# imx6_power.net
KiCad netlist of a schematic drawn in Altium Designer
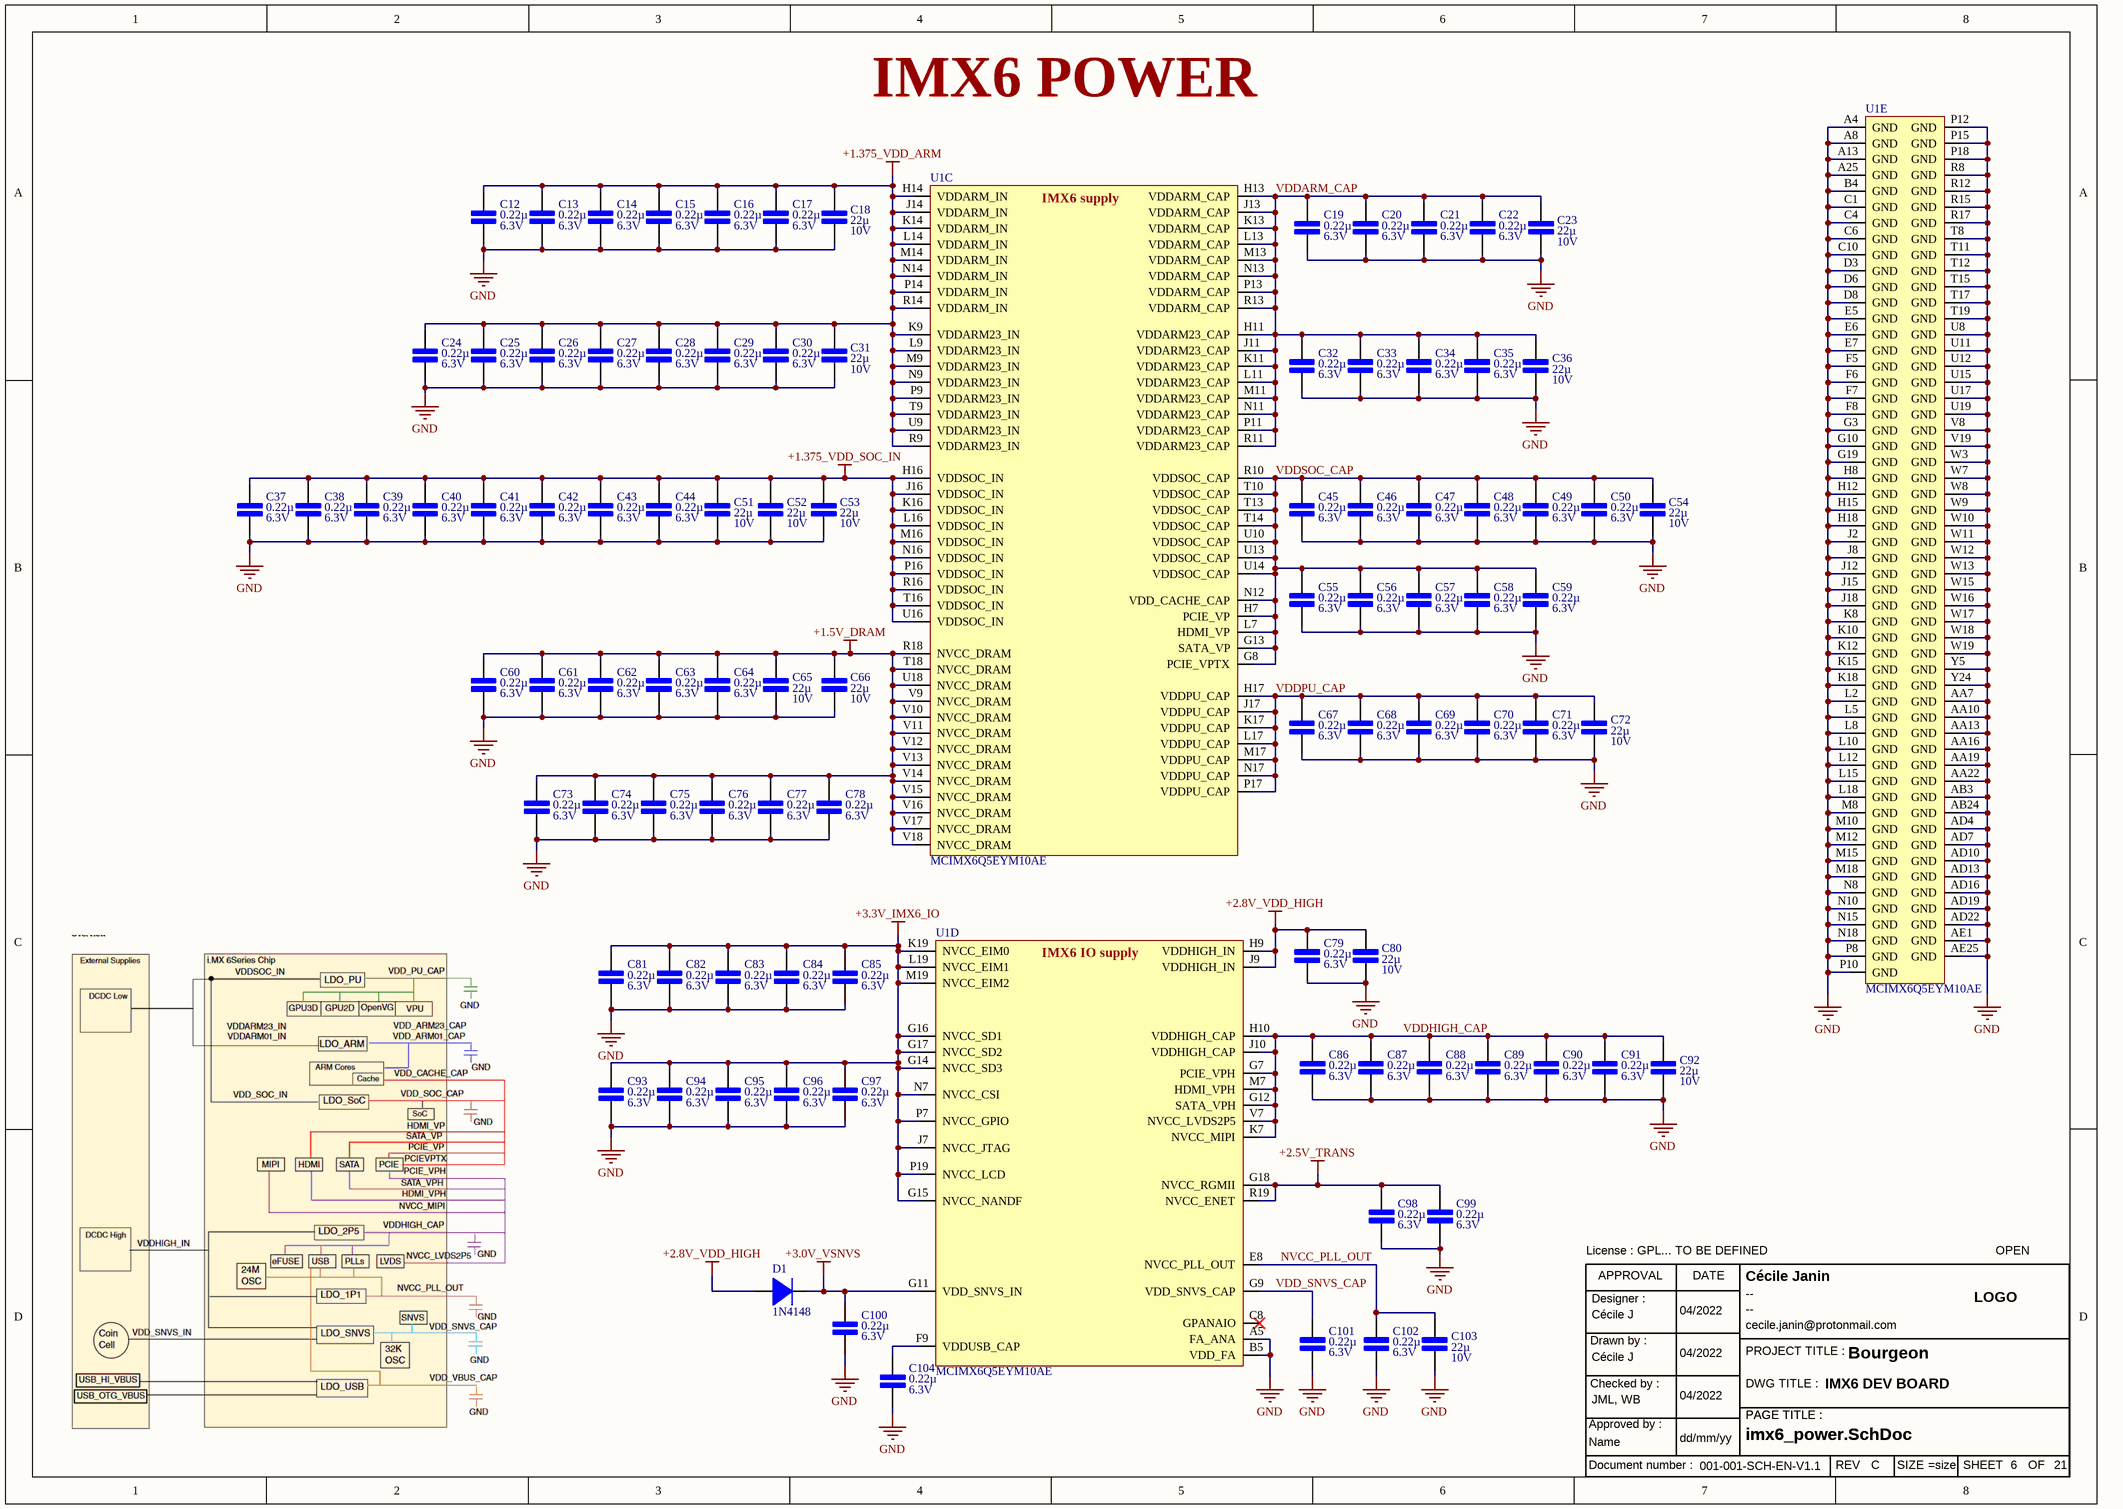
[diagram p0: imx6_power.SchDoc]

(export (version "E")
  (design (tool "Eeschema 10.0.6"))
  (components
    (comp (ref "C12")
      (value "0.22µ")
      (footprint "CAP CER 0201/0603")
      (description "cap solid electrolyte 0.22µ 6.3V 10%")
      (fields (field (name "TENSION DU DIÉLECTRIQUE") "6.3V"))
      (libsource (lib "First Board IMX6") (part "cap 0.22µ 6.3V"))
    )
    (comp (ref "C13")
      (value "0.22µ")
      (footprint "CAP CER 0201/0603")
      (description "cap solid electrolyte 0.22µ 6.3V 10%")
      (fields (field (name "TENSION DU DIÉLECTRIQUE") "6.3V"))
      (libsource (lib "First Board IMX6") (part "cap 0.22µ 6.3V"))
    )
    (comp (ref "C14")
      (value "0.22µ")
      (footprint "CAP CER 0201/0603")
      (description "cap solid electrolyte 0.22µ 6.3V 10%")
      (fields (field (name "TENSION DU DIÉLECTRIQUE") "6.3V"))
      (libsource (lib "First Board IMX6") (part "cap 0.22µ 6.3V"))
    )
    (comp (ref "C15")
      (value "0.22µ")
      (footprint "CAP CER 0201/0603")
      (description "cap solid electrolyte 0.22µ 6.3V 10%")
      (fields (field (name "TENSION DU DIÉLECTRIQUE") "6.3V"))
      (libsource (lib "First Board IMX6") (part "cap 0.22µ 6.3V"))
    )
    (comp (ref "C16")
      (value "0.22µ")
      (footprint "CAP CER 0201/0603")
      (description "cap solid electrolyte 0.22µ 6.3V 10%")
      (fields (field (name "TENSION DU DIÉLECTRIQUE") "6.3V"))
      (libsource (lib "First Board IMX6") (part "cap 0.22µ 6.3V"))
    )
    (comp (ref "C17")
      (value "0.22µ")
      (footprint "CAP CER 0201/0603")
      (description "cap solid electrolyte 0.22µ 6.3V 10%")
      (fields (field (name "TENSION DU DIÉLECTRIQUE") "6.3V"))
      (libsource (lib "First Board IMX6") (part "cap 0.22µ 6.3V"))
    )
    (comp (ref "C18")
      (value "22µ")
      (footprint "Cap cer 0603/4608")
      (description "cap cer 22µ 10V 10% X5R 0603")
      (fields (field (name "TENSION DU DIÉLECTRIQUE") "10V"))
      (libsource (lib "First Board IMX6") (part "cap 22µ 10V"))
    )
    (comp (ref "C19")
      (value "0.22µ")
      (footprint "CAP CER 0201/0603")
      (description "cap solid electrolyte 0.22µ 6.3V 10%")
      (fields (field (name "TENSION DU DIÉLECTRIQUE") "6.3V"))
      (libsource (lib "First Board IMX6") (part "cap 0.22µ 6.3V"))
    )
    (comp (ref "C20")
      (value "0.22µ")
      (footprint "CAP CER 0201/0603")
      (description "cap solid electrolyte 0.22µ 6.3V 10%")
      (fields (field (name "TENSION DU DIÉLECTRIQUE") "6.3V"))
      (libsource (lib "First Board IMX6") (part "cap 0.22µ 6.3V"))
    )
    (comp (ref "C21")
      (value "0.22µ")
      (footprint "CAP CER 0201/0603")
      (description "cap solid electrolyte 0.22µ 6.3V 10%")
      (fields (field (name "TENSION DU DIÉLECTRIQUE") "6.3V"))
      (libsource (lib "First Board IMX6") (part "cap 0.22µ 6.3V"))
    )
    (comp (ref "C22")
      (value "0.22µ")
      (footprint "CAP CER 0201/0603")
      (description "cap solid electrolyte 0.22µ 6.3V 10%")
      (fields (field (name "TENSION DU DIÉLECTRIQUE") "6.3V"))
      (libsource (lib "First Board IMX6") (part "cap 0.22µ 6.3V"))
    )
    (comp (ref "C23")
      (value "22µ")
      (footprint "Cap cer 0603/4608")
      (description "cap cer 22µ 10V 10% X5R 0603")
      (fields (field (name "TENSION DU DIÉLECTRIQUE") "10V"))
      (libsource (lib "First Board IMX6") (part "cap 22µ 10V"))
    )
    (comp (ref "C24")
      (value "0.22µ")
      (footprint "CAP CER 0201/0603")
      (description "cap solid electrolyte 0.22µ 6.3V 10%")
      (fields (field (name "TENSION DU DIÉLECTRIQUE") "6.3V"))
      (libsource (lib "First Board IMX6") (part "cap 0.22µ 6.3V"))
    )
    (comp (ref "C25")
      (value "0.22µ")
      (footprint "CAP CER 0201/0603")
      (description "cap solid electrolyte 0.22µ 6.3V 10%")
      (fields (field (name "TENSION DU DIÉLECTRIQUE") "6.3V"))
      (libsource (lib "First Board IMX6") (part "cap 0.22µ 6.3V"))
    )
    (comp (ref "C26")
      (value "0.22µ")
      (footprint "CAP CER 0201/0603")
      (description "cap solid electrolyte 0.22µ 6.3V 10%")
      (fields (field (name "TENSION DU DIÉLECTRIQUE") "6.3V"))
      (libsource (lib "First Board IMX6") (part "cap 0.22µ 6.3V"))
    )
    (comp (ref "C27")
      (value "0.22µ")
      (footprint "CAP CER 0201/0603")
      (description "cap solid electrolyte 0.22µ 6.3V 10%")
      (fields (field (name "TENSION DU DIÉLECTRIQUE") "6.3V"))
      (libsource (lib "First Board IMX6") (part "cap 0.22µ 6.3V"))
    )
    (comp (ref "C28")
      (value "0.22µ")
      (footprint "CAP CER 0201/0603")
      (description "cap solid electrolyte 0.22µ 6.3V 10%")
      (fields (field (name "TENSION DU DIÉLECTRIQUE") "6.3V"))
      (libsource (lib "First Board IMX6") (part "cap 0.22µ 6.3V"))
    )
    (comp (ref "C29")
      (value "0.22µ")
      (footprint "CAP CER 0201/0603")
      (description "cap solid electrolyte 0.22µ 6.3V 10%")
      (fields (field (name "TENSION DU DIÉLECTRIQUE") "6.3V"))
      (libsource (lib "First Board IMX6") (part "cap 0.22µ 6.3V"))
    )
    (comp (ref "C30")
      (value "0.22µ")
      (footprint "CAP CER 0201/0603")
      (description "cap solid electrolyte 0.22µ 6.3V 10%")
      (fields (field (name "TENSION DU DIÉLECTRIQUE") "6.3V"))
      (libsource (lib "First Board IMX6") (part "cap 0.22µ 6.3V"))
    )
    (comp (ref "C31")
      (value "22µ")
      (footprint "Cap cer 0603/4608")
      (description "cap cer 22µ 10V 10% X5R 0603")
      (fields (field (name "TENSION DU DIÉLECTRIQUE") "10V"))
      (libsource (lib "First Board IMX6") (part "cap 22µ 10V"))
    )
    (comp (ref "C32")
      (value "0.22µ")
      (footprint "CAP CER 0201/0603")
      (description "cap solid electrolyte 0.22µ 6.3V 10%")
      (fields (field (name "TENSION DU DIÉLECTRIQUE") "6.3V"))
      (libsource (lib "First Board IMX6") (part "cap 0.22µ 6.3V"))
    )
    (comp (ref "C33")
      (value "0.22µ")
      (footprint "CAP CER 0201/0603")
      (description "cap solid electrolyte 0.22µ 6.3V 10%")
      (fields (field (name "TENSION DU DIÉLECTRIQUE") "6.3V"))
      (libsource (lib "First Board IMX6") (part "cap 0.22µ 6.3V"))
    )
    (comp (ref "C34")
      (value "0.22µ")
      (footprint "CAP CER 0201/0603")
      (description "cap solid electrolyte 0.22µ 6.3V 10%")
      (fields (field (name "TENSION DU DIÉLECTRIQUE") "6.3V"))
      (libsource (lib "First Board IMX6") (part "cap 0.22µ 6.3V"))
    )
    (comp (ref "C35")
      (value "0.22µ")
      (footprint "CAP CER 0201/0603")
      (description "cap solid electrolyte 0.22µ 6.3V 10%")
      (fields (field (name "TENSION DU DIÉLECTRIQUE") "6.3V"))
      (libsource (lib "First Board IMX6") (part "cap 0.22µ 6.3V"))
    )
    (comp (ref "C36")
      (value "22µ")
      (footprint "Cap cer 0603/4608")
      (description "cap cer 22µ 10V 10% X5R 0603")
      (fields (field (name "TENSION DU DIÉLECTRIQUE") "10V"))
      (libsource (lib "First Board IMX6") (part "cap 22µ 10V"))
    )
    (comp (ref "C37")
      (value "0.22µ")
      (footprint "CAP CER 0201/0603")
      (description "cap solid electrolyte 0.22µ 6.3V 10%")
      (fields (field (name "TENSION DU DIÉLECTRIQUE") "6.3V"))
      (libsource (lib "First Board IMX6") (part "cap 0.22µ 6.3V"))
    )
    (comp (ref "C38")
      (value "0.22µ")
      (footprint "CAP CER 0201/0603")
      (description "cap solid electrolyte 0.22µ 6.3V 10%")
      (fields (field (name "TENSION DU DIÉLECTRIQUE") "6.3V"))
      (libsource (lib "First Board IMX6") (part "cap 0.22µ 6.3V"))
    )
    (comp (ref "C39")
      (value "0.22µ")
      (footprint "CAP CER 0201/0603")
      (description "cap solid electrolyte 0.22µ 6.3V 10%")
      (fields (field (name "TENSION DU DIÉLECTRIQUE") "6.3V"))
      (libsource (lib "First Board IMX6") (part "cap 0.22µ 6.3V"))
    )
    (comp (ref "C40")
      (value "0.22µ")
      (footprint "CAP CER 0201/0603")
      (description "cap solid electrolyte 0.22µ 6.3V 10%")
      (fields (field (name "TENSION DU DIÉLECTRIQUE") "6.3V"))
      (libsource (lib "First Board IMX6") (part "cap 0.22µ 6.3V"))
    )
    (comp (ref "C41")
      (value "0.22µ")
      (footprint "CAP CER 0201/0603")
      (description "cap solid electrolyte 0.22µ 6.3V 10%")
      (fields (field (name "TENSION DU DIÉLECTRIQUE") "6.3V"))
      (libsource (lib "First Board IMX6") (part "cap 0.22µ 6.3V"))
    )
    (comp (ref "C42")
      (value "0.22µ")
      (footprint "CAP CER 0201/0603")
      (description "cap solid electrolyte 0.22µ 6.3V 10%")
      (fields (field (name "TENSION DU DIÉLECTRIQUE") "6.3V"))
      (libsource (lib "First Board IMX6") (part "cap 0.22µ 6.3V"))
    )
    (comp (ref "C43")
      (value "0.22µ")
      (footprint "CAP CER 0201/0603")
      (description "cap solid electrolyte 0.22µ 6.3V 10%")
      (fields (field (name "TENSION DU DIÉLECTRIQUE") "6.3V"))
      (libsource (lib "First Board IMX6") (part "cap 0.22µ 6.3V"))
    )
    (comp (ref "C44")
      (value "0.22µ")
      (footprint "CAP CER 0201/0603")
      (description "cap solid electrolyte 0.22µ 6.3V 10%")
      (fields (field (name "TENSION DU DIÉLECTRIQUE") "6.3V"))
      (libsource (lib "First Board IMX6") (part "cap 0.22µ 6.3V"))
    )
    (comp (ref "C45")
      (value "0.22µ")
      (footprint "CAP CER 0201/0603")
      (description "cap solid electrolyte 0.22µ 6.3V 10%")
      (fields (field (name "TENSION DU DIÉLECTRIQUE") "6.3V"))
      (libsource (lib "First Board IMX6") (part "cap 0.22µ 6.3V"))
    )
    (comp (ref "C46")
      (value "0.22µ")
      (footprint "CAP CER 0201/0603")
      (description "cap solid electrolyte 0.22µ 6.3V 10%")
      (fields (field (name "TENSION DU DIÉLECTRIQUE") "6.3V"))
      (libsource (lib "First Board IMX6") (part "cap 0.22µ 6.3V"))
    )
    (comp (ref "C47")
      (value "0.22µ")
      (footprint "CAP CER 0201/0603")
      (description "cap solid electrolyte 0.22µ 6.3V 10%")
      (fields (field (name "TENSION DU DIÉLECTRIQUE") "6.3V"))
      (libsource (lib "First Board IMX6") (part "cap 0.22µ 6.3V"))
    )
    (comp (ref "C48")
      (value "0.22µ")
      (footprint "CAP CER 0201/0603")
      (description "cap solid electrolyte 0.22µ 6.3V 10%")
      (fields (field (name "TENSION DU DIÉLECTRIQUE") "6.3V"))
      (libsource (lib "First Board IMX6") (part "cap 0.22µ 6.3V"))
    )
    (comp (ref "C49")
      (value "0.22µ")
      (footprint "CAP CER 0201/0603")
      (description "cap solid electrolyte 0.22µ 6.3V 10%")
      (fields (field (name "TENSION DU DIÉLECTRIQUE") "6.3V"))
      (libsource (lib "First Board IMX6") (part "cap 0.22µ 6.3V"))
    )
    (comp (ref "C50")
      (value "0.22µ")
      (footprint "CAP CER 0201/0603")
      (description "cap solid electrolyte 0.22µ 6.3V 10%")
      (fields (field (name "TENSION DU DIÉLECTRIQUE") "6.3V"))
      (libsource (lib "First Board IMX6") (part "cap 0.22µ 6.3V"))
    )
    (comp (ref "C51")
      (value "22µ")
      (footprint "Cap cer 0603/4608")
      (description "cap cer 22µ 10V 10% X5R 0603")
      (fields (field (name "TENSION DU DIÉLECTRIQUE") "10V"))
      (libsource (lib "First Board IMX6") (part "cap 22µ 10V"))
    )
    (comp (ref "C52")
      (value "22µ")
      (footprint "Cap cer 0603/4608")
      (description "cap cer 22µ 10V 10% X5R 0603")
      (fields (field (name "TENSION DU DIÉLECTRIQUE") "10V"))
      (libsource (lib "First Board IMX6") (part "cap 22µ 10V"))
    )
    (comp (ref "C53")
      (value "22µ")
      (footprint "Cap cer 0603/4608")
      (description "cap cer 22µ 10V 10% X5R 0603")
      (fields (field (name "TENSION DU DIÉLECTRIQUE") "10V"))
      (libsource (lib "First Board IMX6") (part "cap 22µ 10V"))
    )
    (comp (ref "C54")
      (value "22µ")
      (footprint "Cap cer 0603/4608")
      (description "cap cer 22µ 10V 10% X5R 0603")
      (fields (field (name "TENSION DU DIÉLECTRIQUE") "10V"))
      (libsource (lib "First Board IMX6") (part "cap 22µ 10V"))
    )
    (comp (ref "C55")
      (value "0.22µ")
      (footprint "CAP CER 0201/0603")
      (description "cap solid electrolyte 0.22µ 6.3V 10%")
      (fields (field (name "TENSION DU DIÉLECTRIQUE") "6.3V"))
      (libsource (lib "First Board IMX6") (part "cap 0.22µ 6.3V"))
    )
    (comp (ref "C56")
      (value "0.22µ")
      (footprint "CAP CER 0201/0603")
      (description "cap solid electrolyte 0.22µ 6.3V 10%")
      (fields (field (name "TENSION DU DIÉLECTRIQUE") "6.3V"))
      (libsource (lib "First Board IMX6") (part "cap 0.22µ 6.3V"))
    )
    (comp (ref "C57")
      (value "0.22µ")
      (footprint "CAP CER 0201/0603")
      (description "cap solid electrolyte 0.22µ 6.3V 10%")
      (fields (field (name "TENSION DU DIÉLECTRIQUE") "6.3V"))
      (libsource (lib "First Board IMX6") (part "cap 0.22µ 6.3V"))
    )
    (comp (ref "C58")
      (value "0.22µ")
      (footprint "CAP CER 0201/0603")
      (description "cap solid electrolyte 0.22µ 6.3V 10%")
      (fields (field (name "TENSION DU DIÉLECTRIQUE") "6.3V"))
      (libsource (lib "First Board IMX6") (part "cap 0.22µ 6.3V"))
    )
    (comp (ref "C59")
      (value "0.22µ")
      (footprint "CAP CER 0201/0603")
      (description "cap solid electrolyte 0.22µ 6.3V 10%")
      (fields (field (name "TENSION DU DIÉLECTRIQUE") "6.3V"))
      (libsource (lib "First Board IMX6") (part "cap 0.22µ 6.3V"))
    )
    (comp (ref "C60")
      (value "0.22µ")
      (footprint "CAP CER 0201/0603")
      (description "cap solid electrolyte 0.22µ 6.3V 10%")
      (fields (field (name "TENSION DU DIÉLECTRIQUE") "6.3V"))
      (libsource (lib "First Board IMX6") (part "cap 0.22µ 6.3V"))
    )
    (comp (ref "C61")
      (value "0.22µ")
      (footprint "CAP CER 0201/0603")
      (description "cap solid electrolyte 0.22µ 6.3V 10%")
      (fields (field (name "TENSION DU DIÉLECTRIQUE") "6.3V"))
      (libsource (lib "First Board IMX6") (part "cap 0.22µ 6.3V"))
    )
    (comp (ref "C62")
      (value "0.22µ")
      (footprint "CAP CER 0201/0603")
      (description "cap solid electrolyte 0.22µ 6.3V 10%")
      (fields (field (name "TENSION DU DIÉLECTRIQUE") "6.3V"))
      (libsource (lib "First Board IMX6") (part "cap 0.22µ 6.3V"))
    )
    (comp (ref "C63")
      (value "0.22µ")
      (footprint "CAP CER 0201/0603")
      (description "cap solid electrolyte 0.22µ 6.3V 10%")
      (fields (field (name "TENSION DU DIÉLECTRIQUE") "6.3V"))
      (libsource (lib "First Board IMX6") (part "cap 0.22µ 6.3V"))
    )
    (comp (ref "C64")
      (value "0.22µ")
      (footprint "CAP CER 0201/0603")
      (description "cap solid electrolyte 0.22µ 6.3V 10%")
      (fields (field (name "TENSION DU DIÉLECTRIQUE") "6.3V"))
      (libsource (lib "First Board IMX6") (part "cap 0.22µ 6.3V"))
    )
    (comp (ref "C65")
      (value "22µ")
      (footprint "Cap cer 0603/4608")
      (description "cap cer 22µ 10V 10% X5R 0603")
      (fields (field (name "TENSION DU DIÉLECTRIQUE") "10V"))
      (libsource (lib "First Board IMX6") (part "cap 22µ 10V"))
    )
    (comp (ref "C66")
      (value "22µ")
      (footprint "Cap cer 0603/4608")
      (description "cap cer 22µ 10V 10% X5R 0603")
      (fields (field (name "TENSION DU DIÉLECTRIQUE") "10V"))
      (libsource (lib "First Board IMX6") (part "cap 22µ 10V"))
    )
    (comp (ref "C67")
      (value "0.22µ")
      (footprint "CAP CER 0201/0603")
      (description "cap solid electrolyte 0.22µ 6.3V 10%")
      (fields (field (name "TENSION DU DIÉLECTRIQUE") "6.3V"))
      (libsource (lib "First Board IMX6") (part "cap 0.22µ 6.3V"))
    )
    (comp (ref "C68")
      (value "0.22µ")
      (footprint "CAP CER 0201/0603")
      (description "cap solid electrolyte 0.22µ 6.3V 10%")
      (fields (field (name "TENSION DU DIÉLECTRIQUE") "6.3V"))
      (libsource (lib "First Board IMX6") (part "cap 0.22µ 6.3V"))
    )
    (comp (ref "C69")
      (value "0.22µ")
      (footprint "CAP CER 0201/0603")
      (description "cap solid electrolyte 0.22µ 6.3V 10%")
      (fields (field (name "TENSION DU DIÉLECTRIQUE") "6.3V"))
      (libsource (lib "First Board IMX6") (part "cap 0.22µ 6.3V"))
    )
    (comp (ref "C70")
      (value "0.22µ")
      (footprint "CAP CER 0201/0603")
      (description "cap solid electrolyte 0.22µ 6.3V 10%")
      (fields (field (name "TENSION DU DIÉLECTRIQUE") "6.3V"))
      (libsource (lib "First Board IMX6") (part "cap 0.22µ 6.3V"))
    )
    (comp (ref "C71")
      (value "0.22µ")
      (footprint "CAP CER 0201/0603")
      (description "cap solid electrolyte 0.22µ 6.3V 10%")
      (fields (field (name "TENSION DU DIÉLECTRIQUE") "6.3V"))
      (libsource (lib "First Board IMX6") (part "cap 0.22µ 6.3V"))
    )
    (comp (ref "C72")
      (value "22µ")
      (footprint "Cap cer 0603/4608")
      (description "cap cer 22µ 10V 10% X5R 0603")
      (fields (field (name "TENSION DU DIÉLECTRIQUE") "10V"))
      (libsource (lib "First Board IMX6") (part "cap 22µ 10V"))
    )
    (comp (ref "C73")
      (value "0.22µ")
      (footprint "CAP CER 0201/0603")
      (description "cap solid electrolyte 0.22µ 6.3V 10%")
      (fields (field (name "TENSION DU DIÉLECTRIQUE") "6.3V"))
      (libsource (lib "First Board IMX6") (part "cap 0.22µ 6.3V"))
    )
    (comp (ref "C74")
      (value "0.22µ")
      (footprint "CAP CER 0201/0603")
      (description "cap solid electrolyte 0.22µ 6.3V 10%")
      (fields (field (name "TENSION DU DIÉLECTRIQUE") "6.3V"))
      (libsource (lib "First Board IMX6") (part "cap 0.22µ 6.3V"))
    )
    (comp (ref "C75")
      (value "0.22µ")
      (footprint "CAP CER 0201/0603")
      (description "cap solid electrolyte 0.22µ 6.3V 10%")
      (fields (field (name "TENSION DU DIÉLECTRIQUE") "6.3V"))
      (libsource (lib "First Board IMX6") (part "cap 0.22µ 6.3V"))
    )
    (comp (ref "C76")
      (value "0.22µ")
      (footprint "CAP CER 0201/0603")
      (description "cap solid electrolyte 0.22µ 6.3V 10%")
      (fields (field (name "TENSION DU DIÉLECTRIQUE") "6.3V"))
      (libsource (lib "First Board IMX6") (part "cap 0.22µ 6.3V"))
    )
    (comp (ref "C77")
      (value "0.22µ")
      (footprint "CAP CER 0201/0603")
      (description "cap solid electrolyte 0.22µ 6.3V 10%")
      (fields (field (name "TENSION DU DIÉLECTRIQUE") "6.3V"))
      (libsource (lib "First Board IMX6") (part "cap 0.22µ 6.3V"))
    )
    (comp (ref "C78")
      (value "0.22µ")
      (footprint "CAP CER 0201/0603")
      (description "cap solid electrolyte 0.22µ 6.3V 10%")
      (fields (field (name "TENSION DU DIÉLECTRIQUE") "6.3V"))
      (libsource (lib "First Board IMX6") (part "cap 0.22µ 6.3V"))
    )
    (comp (ref "C79")
      (value "0.22µ")
      (footprint "CAP CER 0201/0603")
      (description "cap solid electrolyte 0.22µ 6.3V 10%")
      (fields (field (name "TENSION DU DIÉLECTRIQUE") "6.3V"))
      (libsource (lib "First Board IMX6") (part "cap 0.22µ 6.3V"))
    )
    (comp (ref "C80")
      (value "22µ")
      (footprint "Cap cer 0603/4608")
      (description "cap cer 22µ 10V 10% X5R 0603")
      (fields (field (name "TENSION DU DIÉLECTRIQUE") "10V"))
      (libsource (lib "First Board IMX6") (part "cap 22µ 10V"))
    )
    (comp (ref "C81")
      (value "0.22µ")
      (footprint "CAP CER 0201/0603")
      (description "cap solid electrolyte 0.22µ 6.3V 10%")
      (fields (field (name "TENSION DU DIÉLECTRIQUE") "6.3V"))
      (libsource (lib "First Board IMX6") (part "cap 0.22µ 6.3V"))
    )
    (comp (ref "C82")
      (value "0.22µ")
      (footprint "CAP CER 0201/0603")
      (description "cap solid electrolyte 0.22µ 6.3V 10%")
      (fields (field (name "TENSION DU DIÉLECTRIQUE") "6.3V"))
      (libsource (lib "First Board IMX6") (part "cap 0.22µ 6.3V"))
    )
    (comp (ref "C83")
      (value "0.22µ")
      (footprint "CAP CER 0201/0603")
      (description "cap solid electrolyte 0.22µ 6.3V 10%")
      (fields (field (name "TENSION DU DIÉLECTRIQUE") "6.3V"))
      (libsource (lib "First Board IMX6") (part "cap 0.22µ 6.3V"))
    )
    (comp (ref "C84")
      (value "0.22µ")
      (footprint "CAP CER 0201/0603")
      (description "cap solid electrolyte 0.22µ 6.3V 10%")
      (fields (field (name "TENSION DU DIÉLECTRIQUE") "6.3V"))
      (libsource (lib "First Board IMX6") (part "cap 0.22µ 6.3V"))
    )
    (comp (ref "C85")
      (value "0.22µ")
      (footprint "CAP CER 0201/0603")
      (description "cap solid electrolyte 0.22µ 6.3V 10%")
      (fields (field (name "TENSION DU DIÉLECTRIQUE") "6.3V"))
      (libsource (lib "First Board IMX6") (part "cap 0.22µ 6.3V"))
    )
    (comp (ref "C86")
      (value "0.22µ")
      (footprint "CAP CER 0201/0603")
      (description "cap solid electrolyte 0.22µ 6.3V 10%")
      (fields (field (name "TENSION DU DIÉLECTRIQUE") "6.3V"))
      (libsource (lib "First Board IMX6") (part "cap 0.22µ 6.3V"))
    )
    (comp (ref "C87")
      (value "0.22µ")
      (footprint "CAP CER 0201/0603")
      (description "cap solid electrolyte 0.22µ 6.3V 10%")
      (fields (field (name "TENSION DU DIÉLECTRIQUE") "6.3V"))
      (libsource (lib "First Board IMX6") (part "cap 0.22µ 6.3V"))
    )
    (comp (ref "C88")
      (value "0.22µ")
      (footprint "CAP CER 0201/0603")
      (description "cap solid electrolyte 0.22µ 6.3V 10%")
      (fields (field (name "TENSION DU DIÉLECTRIQUE") "6.3V"))
      (libsource (lib "First Board IMX6") (part "cap 0.22µ 6.3V"))
    )
    (comp (ref "C89")
      (value "0.22µ")
      (footprint "CAP CER 0201/0603")
      (description "cap solid electrolyte 0.22µ 6.3V 10%")
      (fields (field (name "TENSION DU DIÉLECTRIQUE") "6.3V"))
      (libsource (lib "First Board IMX6") (part "cap 0.22µ 6.3V"))
    )
    (comp (ref "C90")
      (value "0.22µ")
      (footprint "CAP CER 0201/0603")
      (description "cap solid electrolyte 0.22µ 6.3V 10%")
      (fields (field (name "TENSION DU DIÉLECTRIQUE") "6.3V"))
      (libsource (lib "First Board IMX6") (part "cap 0.22µ 6.3V"))
    )
    (comp (ref "C91")
      (value "0.22µ")
      (footprint "CAP CER 0201/0603")
      (description "cap solid electrolyte 0.22µ 6.3V 10%")
      (fields (field (name "TENSION DU DIÉLECTRIQUE") "6.3V"))
      (libsource (lib "First Board IMX6") (part "cap 0.22µ 6.3V"))
    )
    (comp (ref "C92")
      (value "22µ")
      (footprint "Cap cer 0603/4608")
      (description "cap cer 22µ 10V 10% X5R 0603")
      (fields (field (name "TENSION DU DIÉLECTRIQUE") "10V"))
      (libsource (lib "First Board IMX6") (part "cap 22µ 10V"))
    )
    (comp (ref "C93")
      (value "0.22µ")
      (footprint "CAP CER 0201/0603")
      (description "cap solid electrolyte 0.22µ 6.3V 10%")
      (fields (field (name "TENSION DU DIÉLECTRIQUE") "6.3V"))
      (libsource (lib "First Board IMX6") (part "cap 0.22µ 6.3V"))
    )
    (comp (ref "C94")
      (value "0.22µ")
      (footprint "CAP CER 0201/0603")
      (description "cap solid electrolyte 0.22µ 6.3V 10%")
      (fields (field (name "TENSION DU DIÉLECTRIQUE") "6.3V"))
      (libsource (lib "First Board IMX6") (part "cap 0.22µ 6.3V"))
    )
    (comp (ref "C95")
      (value "0.22µ")
      (footprint "CAP CER 0201/0603")
      (description "cap solid electrolyte 0.22µ 6.3V 10%")
      (fields (field (name "TENSION DU DIÉLECTRIQUE") "6.3V"))
      (libsource (lib "First Board IMX6") (part "cap 0.22µ 6.3V"))
    )
    (comp (ref "C96")
      (value "0.22µ")
      (footprint "CAP CER 0201/0603")
      (description "cap solid electrolyte 0.22µ 6.3V 10%")
      (fields (field (name "TENSION DU DIÉLECTRIQUE") "6.3V"))
      (libsource (lib "First Board IMX6") (part "cap 0.22µ 6.3V"))
    )
    (comp (ref "C97")
      (value "0.22µ")
      (footprint "CAP CER 0201/0603")
      (description "cap solid electrolyte 0.22µ 6.3V 10%")
      (fields (field (name "TENSION DU DIÉLECTRIQUE") "6.3V"))
      (libsource (lib "First Board IMX6") (part "cap 0.22µ 6.3V"))
    )
    (comp (ref "C98")
      (value "0.22µ")
      (footprint "CAP CER 0201/0603")
      (description "cap solid electrolyte 0.22µ 6.3V 10%")
      (fields (field (name "TENSION DU DIÉLECTRIQUE") "6.3V"))
      (libsource (lib "First Board IMX6") (part "cap 0.22µ 6.3V"))
    )
    (comp (ref "C99")
      (value "0.22µ")
      (footprint "CAP CER 0201/0603")
      (description "cap solid electrolyte 0.22µ 6.3V 10%")
      (fields (field (name "TENSION DU DIÉLECTRIQUE") "6.3V"))
      (libsource (lib "First Board IMX6") (part "cap 0.22µ 6.3V"))
    )
    (comp (ref "C100")
      (value "0.22µ")
      (footprint "CAP CER 0201/0603")
      (description "cap solid electrolyte 0.22µ 6.3V 10%")
      (fields (field (name "TENSION DU DIÉLECTRIQUE") "6.3V"))
      (libsource (lib "First Board IMX6") (part "cap 0.22µ 6.3V"))
    )
    (comp (ref "C101")
      (value "0.22µ")
      (footprint "CAP CER 0201/0603")
      (description "cap solid electrolyte 0.22µ 6.3V 10%")
      (fields (field (name "TENSION DU DIÉLECTRIQUE") "6.3V"))
      (libsource (lib "First Board IMX6") (part "cap 0.22µ 6.3V"))
    )
    (comp (ref "C102")
      (value "0.22µ")
      (footprint "CAP CER 0201/0603")
      (description "cap solid electrolyte 0.22µ 6.3V 10%")
      (fields (field (name "TENSION DU DIÉLECTRIQUE") "6.3V"))
      (libsource (lib "First Board IMX6") (part "cap 0.22µ 6.3V"))
    )
    (comp (ref "C103")
      (value "22µ")
      (footprint "Cap cer 0603/4608")
      (description "cap cer 22µ 10V 10% X5R 0603")
      (fields (field (name "TENSION DU DIÉLECTRIQUE") "10V"))
      (libsource (lib "First Board IMX6") (part "cap 22µ 10V"))
    )
    (comp (ref "C104")
      (value "0.22µ")
      (footprint "CAP CER 0201/0603")
      (description "cap solid electrolyte 0.22µ 6.3V 10%")
      (fields (field (name "TENSION DU DIÉLECTRIQUE") "6.3V"))
      (libsource (lib "First Board IMX6") (part "cap 0.22µ 6.3V"))
    )
    (comp (ref "D1")
      (value "1N4148")
      (footprint "diode SOD-123")
      (libsource (lib "First Board IMX6") (part "Diode 1N4148 100V 150mA"))
    )
    (comp (ref "TB4")
      (value "Title bloc ANSI modified")
      (libsource (lib "First Board IMX6") (part "Title bloc ANSI"))
    )
    (comp (ref "U1")
      (value "MCIMX6Q5EYM10AE")
      (footprint "FRES-2197-01")
      (fields
        (field (name "PARTNUMBER") "MCIMX6Q5EYM10ACR")
        (field (name "MANUFACTURER") "Freescale Semiconductor")
      )
      (libsource (lib "First Board IMX6") (part "IMX6Q5EYM10AE"))
    )
  )
  (nets
    (net (code "1") (name "+1.5V_DRAM") (class "Default")
      (node (ref "C60") (pin "1") (pinfunction "3_1") (pintype "passive"))
      (node (ref "C61") (pin "1") (pinfunction "3_1") (pintype "passive"))
      (node (ref "C62") (pin "1") (pinfunction "3_1") (pintype "passive"))
      (node (ref "C63") (pin "1") (pinfunction "3_1") (pintype "passive"))
      (node (ref "C64") (pin "1") (pinfunction "3_1") (pintype "passive"))
      (node (ref "C65") (pin "1") (pinfunction "3_1") (pintype "passive"))
      (node (ref "C66") (pin "1") (pinfunction "3_1") (pintype "passive"))
      (node (ref "C73") (pin "1") (pinfunction "3_1") (pintype "passive"))
      (node (ref "C74") (pin "1") (pinfunction "3_1") (pintype "passive"))
      (node (ref "C75") (pin "1") (pinfunction "3_1") (pintype "passive"))
      (node (ref "C76") (pin "1") (pinfunction "3_1") (pintype "passive"))
      (node (ref "C77") (pin "1") (pinfunction "3_1") (pintype "passive"))
      (node (ref "C78") (pin "1") (pinfunction "3_1") (pintype "passive"))
      (node (ref "U1") (pin "R18") (pinfunction "NVCC_DRAM_R18") (pintype "power_in"))
      (node (ref "U1") (pin "T18") (pinfunction "NVCC_DRAM_T18") (pintype "power_in"))
      (node (ref "U1") (pin "U18") (pinfunction "NVCC_DRAM_U18") (pintype "power_in"))
      (node (ref "U1") (pin "V10") (pinfunction "NVCC_DRAM_V10") (pintype "power_in"))
      (node (ref "U1") (pin "V11") (pinfunction "NVCC_DRAM_V11") (pintype "power_in"))
      (node (ref "U1") (pin "V12") (pinfunction "NVCC_DRAM_V12") (pintype "power_in"))
      (node (ref "U1") (pin "V13") (pinfunction "NVCC_DRAM_V13") (pintype "power_in"))
      (node (ref "U1") (pin "V14") (pinfunction "NVCC_DRAM_V14") (pintype "power_in"))
      (node (ref "U1") (pin "V15") (pinfunction "NVCC_DRAM_V15") (pintype "power_in"))
      (node (ref "U1") (pin "V16") (pinfunction "NVCC_DRAM_V16") (pintype "power_in"))
      (node (ref "U1") (pin "V17") (pinfunction "NVCC_DRAM_V17") (pintype "power_in"))
      (node (ref "U1") (pin "V18") (pinfunction "NVCC_DRAM_V18") (pintype "power_in"))
      (node (ref "U1") (pin "V9") (pinfunction "NVCC_DRAM_V9") (pintype "power_in"))
    )
    (net (code "2") (name "+1.375_VDD_ARM") (class "Default")
      (node (ref "C12") (pin "1") (pinfunction "3_1") (pintype "passive"))
      (node (ref "C13") (pin "1") (pinfunction "3_1") (pintype "passive"))
      (node (ref "C14") (pin "1") (pinfunction "3_1") (pintype "passive"))
      (node (ref "C15") (pin "1") (pinfunction "3_1") (pintype "passive"))
      (node (ref "C16") (pin "1") (pinfunction "3_1") (pintype "passive"))
      (node (ref "C17") (pin "1") (pinfunction "3_1") (pintype "passive"))
      (node (ref "C18") (pin "1") (pinfunction "3_1") (pintype "passive"))
      (node (ref "C24") (pin "1") (pinfunction "3_1") (pintype "passive"))
      (node (ref "C25") (pin "1") (pinfunction "3_1") (pintype "passive"))
      (node (ref "C26") (pin "1") (pinfunction "3_1") (pintype "passive"))
      (node (ref "C27") (pin "1") (pinfunction "3_1") (pintype "passive"))
      (node (ref "C28") (pin "1") (pinfunction "3_1") (pintype "passive"))
      (node (ref "C29") (pin "1") (pinfunction "3_1") (pintype "passive"))
      (node (ref "C30") (pin "1") (pinfunction "3_1") (pintype "passive"))
      (node (ref "C31") (pin "1") (pinfunction "3_1") (pintype "passive"))
      (node (ref "U1") (pin "H14") (pinfunction "VDDARM_IN_H14") (pintype "power_in"))
      (node (ref "U1") (pin "J14") (pinfunction "VDDARM_IN_J14") (pintype "power_in"))
      (node (ref "U1") (pin "K14") (pinfunction "VDDARM_IN_K14") (pintype "power_in"))
      (node (ref "U1") (pin "K9") (pinfunction "VDDARM23_IN_K9") (pintype "power_in"))
      (node (ref "U1") (pin "L14") (pinfunction "VDDARM_IN_L14") (pintype "power_in"))
      (node (ref "U1") (pin "L9") (pinfunction "VDDARM23_IN_L9") (pintype "power_in"))
      (node (ref "U1") (pin "M14") (pinfunction "VDDARM_IN_M14") (pintype "power_in"))
      (node (ref "U1") (pin "M9") (pinfunction "VDDARM23_IN_M9") (pintype "power_in"))
      (node (ref "U1") (pin "N14") (pinfunction "VDDARM_IN_N14") (pintype "power_in"))
      (node (ref "U1") (pin "N9") (pinfunction "VDDARM23_IN_N9") (pintype "power_in"))
      (node (ref "U1") (pin "P14") (pinfunction "VDDARM_IN_P14") (pintype "power_in"))
      (node (ref "U1") (pin "P9") (pinfunction "VDDARM23_IN_P9") (pintype "power_in"))
      (node (ref "U1") (pin "R14") (pinfunction "VDDARM_IN_R14") (pintype "power_in"))
      (node (ref "U1") (pin "R9") (pinfunction "VDDARM23_IN_R9") (pintype "power_in"))
      (node (ref "U1") (pin "T9") (pinfunction "VDDARM23_IN_T9") (pintype "power_in"))
      (node (ref "U1") (pin "U9") (pinfunction "VDDARM23_IN_U9") (pintype "power_in"))
    )
    (net (code "3") (name "+1.375_VDD_SOC_IN") (class "Default")
      (node (ref "C37") (pin "1") (pinfunction "3_1") (pintype "passive"))
      (node (ref "C38") (pin "1") (pinfunction "3_1") (pintype "passive"))
      (node (ref "C39") (pin "1") (pinfunction "3_1") (pintype "passive"))
      (node (ref "C40") (pin "1") (pinfunction "3_1") (pintype "passive"))
      (node (ref "C41") (pin "1") (pinfunction "3_1") (pintype "passive"))
      (node (ref "C42") (pin "1") (pinfunction "3_1") (pintype "passive"))
      (node (ref "C43") (pin "1") (pinfunction "3_1") (pintype "passive"))
      (node (ref "C44") (pin "1") (pinfunction "3_1") (pintype "passive"))
      (node (ref "C51") (pin "1") (pinfunction "3_1") (pintype "passive"))
      (node (ref "C52") (pin "1") (pinfunction "3_1") (pintype "passive"))
      (node (ref "C53") (pin "1") (pinfunction "3_1") (pintype "passive"))
      (node (ref "U1") (pin "H16") (pinfunction "VDDSOC_IN_H16") (pintype "power_in"))
      (node (ref "U1") (pin "J16") (pinfunction "VDDSOC_IN_J16") (pintype "power_in"))
      (node (ref "U1") (pin "K16") (pinfunction "VDDSOC_IN_K16") (pintype "power_in"))
      (node (ref "U1") (pin "L16") (pinfunction "VDDSOC_IN_L16") (pintype "power_in"))
      (node (ref "U1") (pin "M16") (pinfunction "VDDSOC_IN_M16") (pintype "power_in"))
      (node (ref "U1") (pin "N16") (pinfunction "VDDSOC_IN_N16") (pintype "power_in"))
      (node (ref "U1") (pin "P16") (pinfunction "VDDSOC_IN_P16") (pintype "power_in"))
      (node (ref "U1") (pin "R16") (pinfunction "VDDSOC_IN_R16") (pintype "power_in"))
      (node (ref "U1") (pin "T16") (pinfunction "VDDSOC_IN_T16") (pintype "power_in"))
      (node (ref "U1") (pin "U16") (pinfunction "VDDSOC_IN_U16") (pintype "power_in"))
    )
    (net (code "4") (name "+2.5V_TRANS") (class "Default")
      (node (ref "C98") (pin "1") (pinfunction "3_1") (pintype "passive"))
      (node (ref "C99") (pin "1") (pinfunction "3_1") (pintype "passive"))
      (node (ref "U1") (pin "G18") (pinfunction "NVCC_RGMII_G18") (pintype "power_in"))
      (node (ref "U1") (pin "R19") (pinfunction "NVCC_ENET_R19") (pintype "power_in"))
    )
    (net (code "5") (name "+2.8V_VDD_HIGH") (class "Default")
      (node (ref "C79") (pin "1") (pinfunction "3_1") (pintype "passive"))
      (node (ref "C80") (pin "1") (pinfunction "3_1") (pintype "passive"))
      (node (ref "D1") (pin "A") (pintype "passive"))
      (node (ref "U1") (pin "H9") (pinfunction "VDDHIGH_IN_H9") (pintype "power_in"))
      (node (ref "U1") (pin "J9") (pinfunction "VDDHIGH_IN_J9") (pintype "power_in"))
    )
    (net (code "6") (name "+3.0V_VSNVS") (class "Default")
      (node (ref "C100") (pin "1") (pinfunction "3_1") (pintype "passive"))
      (node (ref "D1") (pin "K") (pintype "passive"))
      (node (ref "U1") (pin "G11") (pinfunction "VDD_SNVS_IN_G11") (pintype "power_in"))
    )
    (net (code "7") (name "+3.3V_IMX6_IO") (class "Default")
      (node (ref "C81") (pin "1") (pinfunction "3_1") (pintype "passive"))
      (node (ref "C82") (pin "1") (pinfunction "3_1") (pintype "passive"))
      (node (ref "C83") (pin "1") (pinfunction "3_1") (pintype "passive"))
      (node (ref "C84") (pin "1") (pinfunction "3_1") (pintype "passive"))
      (node (ref "C85") (pin "1") (pinfunction "3_1") (pintype "passive"))
      (node (ref "C93") (pin "1") (pinfunction "3_1") (pintype "passive"))
      (node (ref "C94") (pin "1") (pinfunction "3_1") (pintype "passive"))
      (node (ref "C95") (pin "1") (pinfunction "3_1") (pintype "passive"))
      (node (ref "C96") (pin "1") (pinfunction "3_1") (pintype "passive"))
      (node (ref "C97") (pin "1") (pinfunction "3_1") (pintype "passive"))
      (node (ref "U1") (pin "G14") (pinfunction "NVCC_SD3_G14") (pintype "power_in"))
      (node (ref "U1") (pin "G15") (pinfunction "NVCC_NANDF_G15") (pintype "power_in"))
      (node (ref "U1") (pin "G16") (pinfunction "NVCC_SD1_G16") (pintype "power_in"))
      (node (ref "U1") (pin "G17") (pinfunction "NVCC_SD2_G17") (pintype "power_in"))
      (node (ref "U1") (pin "J7") (pinfunction "NVCC_JTAG_J7") (pintype "power_in"))
      (node (ref "U1") (pin "K19") (pinfunction "NVCC_EIM0_K19") (pintype "power_in"))
      (node (ref "U1") (pin "L19") (pinfunction "NVCC_EIM1_L19") (pintype "power_in"))
      (node (ref "U1") (pin "M19") (pinfunction "NVCC_EIM2_M19") (pintype "power_in"))
      (node (ref "U1") (pin "N7") (pinfunction "NVCC_CSI_N7") (pintype "power_in"))
      (node (ref "U1") (pin "P19") (pinfunction "NVCC_LCD_P19") (pintype "power_in"))
      (node (ref "U1") (pin "P7") (pinfunction "NVCC_GPIO_P7") (pintype "power_in"))
    )
    (net (code "8") (name "/NVCC_PLL_OUT") (class "Default")
      (node (ref "C102") (pin "1") (pinfunction "3_1") (pintype "passive"))
      (node (ref "C103") (pin "1") (pinfunction "3_1") (pintype "passive"))
      (node (ref "U1") (pin "E8") (pinfunction "NVCC_PLL_OUT_E8") (pintype "power_in"))
    )
    (net (code "9") (name "/VDDARM_CAP") (class "Default")
      (node (ref "C19") (pin "1") (pinfunction "3_1") (pintype "passive"))
      (node (ref "C20") (pin "1") (pinfunction "3_1") (pintype "passive"))
      (node (ref "C21") (pin "1") (pinfunction "3_1") (pintype "passive"))
      (node (ref "C22") (pin "1") (pinfunction "3_1") (pintype "passive"))
      (node (ref "C23") (pin "1") (pinfunction "3_1") (pintype "passive"))
      (node (ref "C32") (pin "1") (pinfunction "3_1") (pintype "passive"))
      (node (ref "C33") (pin "1") (pinfunction "3_1") (pintype "passive"))
      (node (ref "C34") (pin "1") (pinfunction "3_1") (pintype "passive"))
      (node (ref "C35") (pin "1") (pinfunction "3_1") (pintype "passive"))
      (node (ref "C36") (pin "1") (pinfunction "3_1") (pintype "passive"))
      (node (ref "U1") (pin "H11") (pinfunction "VDDARM23_CAP_H11") (pintype "power_in"))
      (node (ref "U1") (pin "H13") (pinfunction "VDDARM_CAP_H13") (pintype "power_in"))
      (node (ref "U1") (pin "J11") (pinfunction "VDDARM23_CAP_J11") (pintype "power_in"))
      (node (ref "U1") (pin "J13") (pinfunction "VDDARM_CAP_J13") (pintype "power_in"))
      (node (ref "U1") (pin "K11") (pinfunction "VDDARM23_CAP_K11") (pintype "power_in"))
      (node (ref "U1") (pin "K13") (pinfunction "VDDARM_CAP_K13") (pintype "power_in"))
      (node (ref "U1") (pin "L11") (pinfunction "VDDARM23_CAP_L11") (pintype "power_in"))
      (node (ref "U1") (pin "L13") (pinfunction "VDDARM_CAP_L13") (pintype "power_in"))
      (node (ref "U1") (pin "M11") (pinfunction "VDDARM23_CAP_M11") (pintype "power_in"))
      (node (ref "U1") (pin "M13") (pinfunction "VDDARM_CAP_M13") (pintype "power_in"))
      (node (ref "U1") (pin "N11") (pinfunction "VDDARM23_CAP_N11") (pintype "power_in"))
      (node (ref "U1") (pin "N13") (pinfunction "VDDARM_CAP_N13") (pintype "power_in"))
      (node (ref "U1") (pin "P11") (pinfunction "VDDARM23_CAP_P11") (pintype "power_in"))
      (node (ref "U1") (pin "P13") (pinfunction "VDDARM_CAP_P13") (pintype "power_in"))
      (node (ref "U1") (pin "R11") (pinfunction "VDDARM23_CAP_R11") (pintype "power_in"))
      (node (ref "U1") (pin "R13") (pinfunction "VDDARM_CAP_R13") (pintype "power_in"))
    )
    (net (code "10") (name "/VDDHIGH_CAP") (class "Default")
      (node (ref "C86") (pin "1") (pinfunction "3_1") (pintype "passive"))
      (node (ref "C87") (pin "1") (pinfunction "3_1") (pintype "passive"))
      (node (ref "C88") (pin "1") (pinfunction "3_1") (pintype "passive"))
      (node (ref "C89") (pin "1") (pinfunction "3_1") (pintype "passive"))
      (node (ref "C90") (pin "1") (pinfunction "3_1") (pintype "passive"))
      (node (ref "C91") (pin "1") (pinfunction "3_1") (pintype "passive"))
      (node (ref "C92") (pin "1") (pinfunction "3_1") (pintype "passive"))
      (node (ref "U1") (pin "G12") (pinfunction "SATA_VPH_G12") (pintype "power_in"))
      (node (ref "U1") (pin "G7") (pinfunction "PCIE_VPH_G7") (pintype "power_in"))
      (node (ref "U1") (pin "H10") (pinfunction "VDDHIGH_CAP_H10") (pintype "power_in"))
      (node (ref "U1") (pin "J10") (pinfunction "VDDHIGH_CAP_J10") (pintype "power_in"))
      (node (ref "U1") (pin "K7") (pinfunction "NVCC_MIPI_K7") (pintype "power_in"))
      (node (ref "U1") (pin "M7") (pinfunction "HDMI_VPH_M7") (pintype "power_in"))
      (node (ref "U1") (pin "V7") (pinfunction "NVCC_LVDS2P5_V7") (pintype "power_in"))
    )
    (net (code "11") (name "/VDDPU_CAP") (class "Default")
      (node (ref "C67") (pin "1") (pinfunction "3_1") (pintype "passive"))
      (node (ref "C68") (pin "1") (pinfunction "3_1") (pintype "passive"))
      (node (ref "C69") (pin "1") (pinfunction "3_1") (pintype "passive"))
      (node (ref "C70") (pin "1") (pinfunction "3_1") (pintype "passive"))
      (node (ref "C71") (pin "1") (pinfunction "3_1") (pintype "passive"))
      (node (ref "C72") (pin "1") (pinfunction "3_1") (pintype "passive"))
      (node (ref "U1") (pin "H17") (pinfunction "VDDPU_CAP_H17") (pintype "power_in"))
      (node (ref "U1") (pin "J17") (pinfunction "VDDPU_CAP_J17") (pintype "power_in"))
      (node (ref "U1") (pin "K17") (pinfunction "VDDPU_CAP_K17") (pintype "power_in"))
      (node (ref "U1") (pin "L17") (pinfunction "VDDPU_CAP_L17") (pintype "power_in"))
      (node (ref "U1") (pin "M17") (pinfunction "VDDPU_CAP_M17") (pintype "power_in"))
      (node (ref "U1") (pin "N17") (pinfunction "VDDPU_CAP_N17") (pintype "power_in"))
      (node (ref "U1") (pin "P17") (pinfunction "VDDPU_CAP_P17") (pintype "power_in"))
    )
    (net (code "12") (name "/VDDSOC_CAP") (class "Default")
      (node (ref "C45") (pin "1") (pinfunction "3_1") (pintype "passive"))
      (node (ref "C46") (pin "1") (pinfunction "3_1") (pintype "passive"))
      (node (ref "C47") (pin "1") (pinfunction "3_1") (pintype "passive"))
      (node (ref "C48") (pin "1") (pinfunction "3_1") (pintype "passive"))
      (node (ref "C49") (pin "1") (pinfunction "3_1") (pintype "passive"))
      (node (ref "C50") (pin "1") (pinfunction "3_1") (pintype "passive"))
      (node (ref "C54") (pin "1") (pinfunction "3_1") (pintype "passive"))
      (node (ref "C55") (pin "1") (pinfunction "3_1") (pintype "passive"))
      (node (ref "C56") (pin "1") (pinfunction "3_1") (pintype "passive"))
      (node (ref "C57") (pin "1") (pinfunction "3_1") (pintype "passive"))
      (node (ref "C58") (pin "1") (pinfunction "3_1") (pintype "passive"))
      (node (ref "C59") (pin "1") (pinfunction "3_1") (pintype "passive"))
      (node (ref "U1") (pin "G13") (pinfunction "SATA_VP_G13") (pintype "power_in"))
      (node (ref "U1") (pin "G8") (pinfunction "PCIE_VPTX_G8") (pintype "power_in"))
      (node (ref "U1") (pin "H7") (pinfunction "PCIE_VP_H7") (pintype "power_in"))
      (node (ref "U1") (pin "L7") (pinfunction "HDMI_VP_L7") (pintype "power_in"))
      (node (ref "U1") (pin "N12") (pinfunction "VDD_CACHE_CAP_N12") (pintype "power_in"))
      (node (ref "U1") (pin "R10") (pinfunction "VDDSOC_CAP_R10") (pintype "power_in"))
      (node (ref "U1") (pin "T10") (pinfunction "VDDSOC_CAP_T10") (pintype "power_in"))
      (node (ref "U1") (pin "T13") (pinfunction "VDDSOC_CAP_T13") (pintype "power_in"))
      (node (ref "U1") (pin "T14") (pinfunction "VDDSOC_CAP_T14") (pintype "power_in"))
      (node (ref "U1") (pin "U10") (pinfunction "VDDSOC_CAP_U10") (pintype "power_in"))
      (node (ref "U1") (pin "U13") (pinfunction "VDDSOC_CAP_U13") (pintype "power_in"))
      (node (ref "U1") (pin "U14") (pinfunction "VDDSOC_CAP_U14") (pintype "power_in"))
    )
    (net (code "13") (name "/VDD_SNVS_CAP") (class "Default")
      (node (ref "C101") (pin "1") (pinfunction "3_1") (pintype "passive"))
      (node (ref "U1") (pin "G9") (pinfunction "VDD_SNVS_CAP_G9") (pintype "power_in"))
    )
    (net (code "14") (name "GND") (class "Default")
      (node (ref "C100") (pin "2") (pinfunction "4_2") (pintype "passive"))
      (node (ref "C101") (pin "2") (pinfunction "4_2") (pintype "passive"))
      (node (ref "C102") (pin "2") (pinfunction "4_2") (pintype "passive"))
      (node (ref "C103") (pin "2") (pinfunction "4_2") (pintype "passive"))
      (node (ref "C104") (pin "2") (pinfunction "4_2") (pintype "passive"))
      (node (ref "C12") (pin "2") (pinfunction "4_2") (pintype "passive"))
      (node (ref "C13") (pin "2") (pinfunction "4_2") (pintype "passive"))
      (node (ref "C14") (pin "2") (pinfunction "4_2") (pintype "passive"))
      (node (ref "C15") (pin "2") (pinfunction "4_2") (pintype "passive"))
      (node (ref "C16") (pin "2") (pinfunction "4_2") (pintype "passive"))
      (node (ref "C17") (pin "2") (pinfunction "4_2") (pintype "passive"))
      (node (ref "C18") (pin "2") (pinfunction "4_2") (pintype "passive"))
      (node (ref "C19") (pin "2") (pinfunction "4_2") (pintype "passive"))
      (node (ref "C20") (pin "2") (pinfunction "4_2") (pintype "passive"))
      (node (ref "C21") (pin "2") (pinfunction "4_2") (pintype "passive"))
      (node (ref "C22") (pin "2") (pinfunction "4_2") (pintype "passive"))
      (node (ref "C23") (pin "2") (pinfunction "4_2") (pintype "passive"))
      (node (ref "C24") (pin "2") (pinfunction "4_2") (pintype "passive"))
      (node (ref "C25") (pin "2") (pinfunction "4_2") (pintype "passive"))
      (node (ref "C26") (pin "2") (pinfunction "4_2") (pintype "passive"))
      (node (ref "C27") (pin "2") (pinfunction "4_2") (pintype "passive"))
      (node (ref "C28") (pin "2") (pinfunction "4_2") (pintype "passive"))
      (node (ref "C29") (pin "2") (pinfunction "4_2") (pintype "passive"))
      (node (ref "C30") (pin "2") (pinfunction "4_2") (pintype "passive"))
      (node (ref "C31") (pin "2") (pinfunction "4_2") (pintype "passive"))
      (node (ref "C32") (pin "2") (pinfunction "4_2") (pintype "passive"))
      (node (ref "C33") (pin "2") (pinfunction "4_2") (pintype "passive"))
      (node (ref "C34") (pin "2") (pinfunction "4_2") (pintype "passive"))
      (node (ref "C35") (pin "2") (pinfunction "4_2") (pintype "passive"))
      (node (ref "C36") (pin "2") (pinfunction "4_2") (pintype "passive"))
      (node (ref "C37") (pin "2") (pinfunction "4_2") (pintype "passive"))
      (node (ref "C38") (pin "2") (pinfunction "4_2") (pintype "passive"))
      (node (ref "C39") (pin "2") (pinfunction "4_2") (pintype "passive"))
      (node (ref "C40") (pin "2") (pinfunction "4_2") (pintype "passive"))
      (node (ref "C41") (pin "2") (pinfunction "4_2") (pintype "passive"))
      (node (ref "C42") (pin "2") (pinfunction "4_2") (pintype "passive"))
      (node (ref "C43") (pin "2") (pinfunction "4_2") (pintype "passive"))
      (node (ref "C44") (pin "2") (pinfunction "4_2") (pintype "passive"))
      (node (ref "C45") (pin "2") (pinfunction "4_2") (pintype "passive"))
      (node (ref "C46") (pin "2") (pinfunction "4_2") (pintype "passive"))
      (node (ref "C47") (pin "2") (pinfunction "4_2") (pintype "passive"))
      (node (ref "C48") (pin "2") (pinfunction "4_2") (pintype "passive"))
      (node (ref "C49") (pin "2") (pinfunction "4_2") (pintype "passive"))
      (node (ref "C50") (pin "2") (pinfunction "4_2") (pintype "passive"))
      (node (ref "C51") (pin "2") (pinfunction "4_2") (pintype "passive"))
      (node (ref "C52") (pin "2") (pinfunction "4_2") (pintype "passive"))
      (node (ref "C53") (pin "2") (pinfunction "4_2") (pintype "passive"))
      (node (ref "C54") (pin "2") (pinfunction "4_2") (pintype "passive"))
      (node (ref "C55") (pin "2") (pinfunction "4_2") (pintype "passive"))
      (node (ref "C56") (pin "2") (pinfunction "4_2") (pintype "passive"))
      (node (ref "C57") (pin "2") (pinfunction "4_2") (pintype "passive"))
      (node (ref "C58") (pin "2") (pinfunction "4_2") (pintype "passive"))
      (node (ref "C59") (pin "2") (pinfunction "4_2") (pintype "passive"))
      (node (ref "C60") (pin "2") (pinfunction "4_2") (pintype "passive"))
      (node (ref "C61") (pin "2") (pinfunction "4_2") (pintype "passive"))
      (node (ref "C62") (pin "2") (pinfunction "4_2") (pintype "passive"))
      (node (ref "C63") (pin "2") (pinfunction "4_2") (pintype "passive"))
      (node (ref "C64") (pin "2") (pinfunction "4_2") (pintype "passive"))
      (node (ref "C65") (pin "2") (pinfunction "4_2") (pintype "passive"))
      (node (ref "C66") (pin "2") (pinfunction "4_2") (pintype "passive"))
      (node (ref "C67") (pin "2") (pinfunction "4_2") (pintype "passive"))
      (node (ref "C68") (pin "2") (pinfunction "4_2") (pintype "passive"))
      (node (ref "C69") (pin "2") (pinfunction "4_2") (pintype "passive"))
      (node (ref "C70") (pin "2") (pinfunction "4_2") (pintype "passive"))
      (node (ref "C71") (pin "2") (pinfunction "4_2") (pintype "passive"))
      (node (ref "C72") (pin "2") (pinfunction "4_2") (pintype "passive"))
      (node (ref "C73") (pin "2") (pinfunction "4_2") (pintype "passive"))
      (node (ref "C74") (pin "2") (pinfunction "4_2") (pintype "passive"))
      (node (ref "C75") (pin "2") (pinfunction "4_2") (pintype "passive"))
      (node (ref "C76") (pin "2") (pinfunction "4_2") (pintype "passive"))
      (node (ref "C77") (pin "2") (pinfunction "4_2") (pintype "passive"))
      (node (ref "C78") (pin "2") (pinfunction "4_2") (pintype "passive"))
      (node (ref "C79") (pin "2") (pinfunction "4_2") (pintype "passive"))
      (node (ref "C80") (pin "2") (pinfunction "4_2") (pintype "passive"))
      (node (ref "C81") (pin "2") (pinfunction "4_2") (pintype "passive"))
      (node (ref "C82") (pin "2") (pinfunction "4_2") (pintype "passive"))
      (node (ref "C83") (pin "2") (pinfunction "4_2") (pintype "passive"))
      (node (ref "C84") (pin "2") (pinfunction "4_2") (pintype "passive"))
      (node (ref "C85") (pin "2") (pinfunction "4_2") (pintype "passive"))
      (node (ref "C86") (pin "2") (pinfunction "4_2") (pintype "passive"))
      (node (ref "C87") (pin "2") (pinfunction "4_2") (pintype "passive"))
      (node (ref "C88") (pin "2") (pinfunction "4_2") (pintype "passive"))
      (node (ref "C89") (pin "2") (pinfunction "4_2") (pintype "passive"))
      (node (ref "C90") (pin "2") (pinfunction "4_2") (pintype "passive"))
      (node (ref "C91") (pin "2") (pinfunction "4_2") (pintype "passive"))
      (node (ref "C92") (pin "2") (pinfunction "4_2") (pintype "passive"))
      (node (ref "C93") (pin "2") (pinfunction "4_2") (pintype "passive"))
      (node (ref "C94") (pin "2") (pinfunction "4_2") (pintype "passive"))
      (node (ref "C95") (pin "2") (pinfunction "4_2") (pintype "passive"))
      (node (ref "C96") (pin "2") (pinfunction "4_2") (pintype "passive"))
      (node (ref "C97") (pin "2") (pinfunction "4_2") (pintype "passive"))
      (node (ref "C98") (pin "2") (pinfunction "4_2") (pintype "passive"))
      (node (ref "C99") (pin "2") (pinfunction "4_2") (pintype "passive"))
      (node (ref "U1") (pin "A13") (pinfunction "GND_A13") (pintype "power_in"))
      (node (ref "U1") (pin "A25") (pinfunction "GND_A25") (pintype "power_in"))
      (node (ref "U1") (pin "A4") (pinfunction "GND_A4") (pintype "power_in"))
      (node (ref "U1") (pin "A5") (pinfunction "FA_ANA_A5") (pintype "passive"))
      (node (ref "U1") (pin "A8") (pinfunction "GND_A8") (pintype "power_in"))
      (node (ref "U1") (pin "AA10") (pinfunction "GND_AA10") (pintype "power_in"))
      (node (ref "U1") (pin "AA13") (pinfunction "GND_AA13") (pintype "power_in"))
      (node (ref "U1") (pin "AA16") (pinfunction "GND_AA16") (pintype "power_in"))
      (node (ref "U1") (pin "AA19") (pinfunction "GND_AA19") (pintype "power_in"))
      (node (ref "U1") (pin "AA22") (pinfunction "GND_AA22") (pintype "power_in"))
      (node (ref "U1") (pin "AA7") (pinfunction "GND_AA7") (pintype "power_in"))
      (node (ref "U1") (pin "AB24") (pinfunction "GND_AB24") (pintype "power_in"))
      (node (ref "U1") (pin "AB3") (pinfunction "GND_AB3") (pintype "power_in"))
      (node (ref "U1") (pin "AD10") (pinfunction "GND_AD10") (pintype "power_in"))
      (node (ref "U1") (pin "AD13") (pinfunction "GND_AD13") (pintype "power_in"))
      (node (ref "U1") (pin "AD16") (pinfunction "GND_AD16") (pintype "power_in"))
      (node (ref "U1") (pin "AD19") (pinfunction "GND_AD19") (pintype "power_in"))
      (node (ref "U1") (pin "AD22") (pinfunction "GND_AD22") (pintype "power_in"))
      (node (ref "U1") (pin "AD4") (pinfunction "GND_AD4") (pintype "power_in"))
      (node (ref "U1") (pin "AD7") (pinfunction "GND_AD7") (pintype "power_in"))
      (node (ref "U1") (pin "AE1") (pinfunction "GND_AE1") (pintype "power_in"))
      (node (ref "U1") (pin "AE25") (pinfunction "GND_AE25") (pintype "power_in"))
      (node (ref "U1") (pin "B4") (pinfunction "GND_B4") (pintype "power_in"))
      (node (ref "U1") (pin "B5") (pinfunction "VDD_FA_B5") (pintype "power_in"))
      (node (ref "U1") (pin "C1") (pinfunction "GND_C1") (pintype "power_in"))
      (node (ref "U1") (pin "C10") (pinfunction "GND_C10") (pintype "power_in"))
      (node (ref "U1") (pin "C4") (pinfunction "GND_C4") (pintype "power_in"))
      (node (ref "U1") (pin "C6") (pinfunction "GND_C6") (pintype "power_in"))
      (node (ref "U1") (pin "D3") (pinfunction "GND_D3") (pintype "power_in"))
      (node (ref "U1") (pin "D6") (pinfunction "GND_D6") (pintype "power_in"))
      (node (ref "U1") (pin "D8") (pinfunction "GND_D8") (pintype "power_in"))
      (node (ref "U1") (pin "E5") (pinfunction "GND_E5") (pintype "power_in"))
      (node (ref "U1") (pin "E6") (pinfunction "GND_E6") (pintype "power_in"))
      (node (ref "U1") (pin "E7") (pinfunction "GND_E7") (pintype "power_in"))
      (node (ref "U1") (pin "F5") (pinfunction "GND_F5") (pintype "power_in"))
      (node (ref "U1") (pin "F6") (pinfunction "GND_F6") (pintype "power_in"))
      (node (ref "U1") (pin "F7") (pinfunction "GND_F7") (pintype "power_in"))
      (node (ref "U1") (pin "F8") (pinfunction "GND_F8") (pintype "power_in"))
      (node (ref "U1") (pin "G10") (pinfunction "GND_G10") (pintype "power_in"))
      (node (ref "U1") (pin "G19") (pinfunction "GND_G19") (pintype "power_in"))
      (node (ref "U1") (pin "G3") (pinfunction "GND_G3") (pintype "power_in"))
      (node (ref "U1") (pin "H12") (pinfunction "GND_H12") (pintype "power_in"))
      (node (ref "U1") (pin "H15") (pinfunction "GND_H15") (pintype "power_in"))
      (node (ref "U1") (pin "H18") (pinfunction "GND_H18") (pintype "power_in"))
      (node (ref "U1") (pin "H8") (pinfunction "GND_H8") (pintype "power_in"))
      (node (ref "U1") (pin "J12") (pinfunction "GND_J12") (pintype "power_in"))
      (node (ref "U1") (pin "J15") (pinfunction "GND_J15") (pintype "power_in"))
      (node (ref "U1") (pin "J18") (pinfunction "GND_J18") (pintype "power_in"))
      (node (ref "U1") (pin "J2") (pinfunction "GND_J2") (pintype "power_in"))
      (node (ref "U1") (pin "J8") (pinfunction "GND_J8") (pintype "power_in"))
      (node (ref "U1") (pin "K10") (pinfunction "GND_K10") (pintype "power_in"))
      (node (ref "U1") (pin "K12") (pinfunction "GND_K12") (pintype "power_in"))
      (node (ref "U1") (pin "K15") (pinfunction "GND_K15") (pintype "power_in"))
      (node (ref "U1") (pin "K18") (pinfunction "GND_K18") (pintype "power_in"))
      (node (ref "U1") (pin "K8") (pinfunction "GND_K8") (pintype "power_in"))
      (node (ref "U1") (pin "L10") (pinfunction "GND_L10") (pintype "power_in"))
      (node (ref "U1") (pin "L12") (pinfunction "GND_L12") (pintype "power_in"))
      (node (ref "U1") (pin "L15") (pinfunction "GND_L15") (pintype "power_in"))
      (node (ref "U1") (pin "L18") (pinfunction "GND_L18") (pintype "power_in"))
      (node (ref "U1") (pin "L2") (pinfunction "GND_L2") (pintype "power_in"))
      (node (ref "U1") (pin "L5") (pinfunction "GND_L5") (pintype "power_in"))
      (node (ref "U1") (pin "L8") (pinfunction "GND_L8") (pintype "power_in"))
      (node (ref "U1") (pin "M10") (pinfunction "GND_M10") (pintype "power_in"))
      (node (ref "U1") (pin "M12") (pinfunction "GND_M12") (pintype "power_in"))
      (node (ref "U1") (pin "M15") (pinfunction "GND_M15") (pintype "power_in"))
      (node (ref "U1") (pin "M18") (pinfunction "GND_M18") (pintype "power_in"))
      (node (ref "U1") (pin "M8") (pinfunction "GND_M8") (pintype "power_in"))
      (node (ref "U1") (pin "N10") (pinfunction "GND_N10") (pintype "power_in"))
      (node (ref "U1") (pin "N15") (pinfunction "GND_N15") (pintype "power_in"))
      (node (ref "U1") (pin "N18") (pinfunction "GND_N18") (pintype "power_in"))
      (node (ref "U1") (pin "N8") (pinfunction "GND_N8") (pintype "power_in"))
      (node (ref "U1") (pin "P10") (pinfunction "GND_P10") (pintype "power_in"))
      (node (ref "U1") (pin "P12") (pinfunction "GND_P12") (pintype "power_in"))
      (node (ref "U1") (pin "P15") (pinfunction "GND_P15") (pintype "power_in"))
      (node (ref "U1") (pin "P18") (pinfunction "GND_P18") (pintype "power_in"))
      (node (ref "U1") (pin "P8") (pinfunction "GND_P8") (pintype "power_in"))
      (node (ref "U1") (pin "R12") (pinfunction "GND_R12") (pintype "power_in"))
      (node (ref "U1") (pin "R15") (pinfunction "GND_R15") (pintype "power_in"))
      (node (ref "U1") (pin "R17") (pinfunction "GND_R17") (pintype "power_in"))
      (node (ref "U1") (pin "R8") (pinfunction "GND_R8") (pintype "power_in"))
      (node (ref "U1") (pin "T11") (pinfunction "GND_T11") (pintype "power_in"))
      (node (ref "U1") (pin "T12") (pinfunction "GND_T12") (pintype "power_in"))
      (node (ref "U1") (pin "T15") (pinfunction "GND_T15") (pintype "power_in"))
      (node (ref "U1") (pin "T17") (pinfunction "GND_T17") (pintype "power_in"))
      (node (ref "U1") (pin "T19") (pinfunction "GND_T19") (pintype "power_in"))
      (node (ref "U1") (pin "T8") (pinfunction "GND_T8") (pintype "power_in"))
      (node (ref "U1") (pin "U11") (pinfunction "GND_U11") (pintype "power_in"))
      (node (ref "U1") (pin "U12") (pinfunction "GND_U12") (pintype "power_in"))
      (node (ref "U1") (pin "U15") (pinfunction "GND_U15") (pintype "power_in"))
      (node (ref "U1") (pin "U17") (pinfunction "GND_U17") (pintype "power_in"))
      (node (ref "U1") (pin "U19") (pinfunction "GND_U19") (pintype "power_in"))
      (node (ref "U1") (pin "U8") (pinfunction "GND_U8") (pintype "power_in"))
      (node (ref "U1") (pin "V19") (pinfunction "GND_V19") (pintype "power_in"))
      (node (ref "U1") (pin "V8") (pinfunction "GND_V8") (pintype "power_in"))
      (node (ref "U1") (pin "W10") (pinfunction "GND_W10") (pintype "power_in"))
      (node (ref "U1") (pin "W11") (pinfunction "GND_W11") (pintype "power_in"))
      (node (ref "U1") (pin "W12") (pinfunction "GND_W12") (pintype "power_in"))
      (node (ref "U1") (pin "W13") (pinfunction "GND_W13") (pintype "power_in"))
      (node (ref "U1") (pin "W15") (pinfunction "GND_W15") (pintype "power_in"))
      (node (ref "U1") (pin "W16") (pinfunction "GND_W16") (pintype "power_in"))
      (node (ref "U1") (pin "W17") (pinfunction "GND_W17") (pintype "power_in"))
      (node (ref "U1") (pin "W18") (pinfunction "GND_W18") (pintype "power_in"))
      (node (ref "U1") (pin "W19") (pinfunction "GND_W19") (pintype "power_in"))
      (node (ref "U1") (pin "W3") (pinfunction "GND_W3") (pintype "power_in"))
      (node (ref "U1") (pin "W7") (pinfunction "GND_W7") (pintype "power_in"))
      (node (ref "U1") (pin "W8") (pinfunction "GND_W8") (pintype "power_in"))
      (node (ref "U1") (pin "W9") (pinfunction "GND_W9") (pintype "power_in"))
      (node (ref "U1") (pin "Y24") (pinfunction "GND_Y24") (pintype "power_in"))
      (node (ref "U1") (pin "Y5") (pinfunction "GND_Y5") (pintype "power_in"))
    )
    (net (code "15") (name "Net-(C104-3)") (class "Default")
      (node (ref "C104") (pin "1") (pinfunction "3_1") (pintype "passive"))
      (node (ref "U1") (pin "F9") (pinfunction "VDDUSB_CAP_F9") (pintype "power_in"))
    )
    (net (code "16") (name "unconnected-(U1D-GPANAIO-PadC8)") (class "Default")
      (node (ref "U1") (pin "C8") (pinfunction "GPANAIO_C8") (pintype "passive+no_connect"))
    )
  )
)
